# 03_Power.net
KiCad netlist of a schematic drawn in Altium Designer
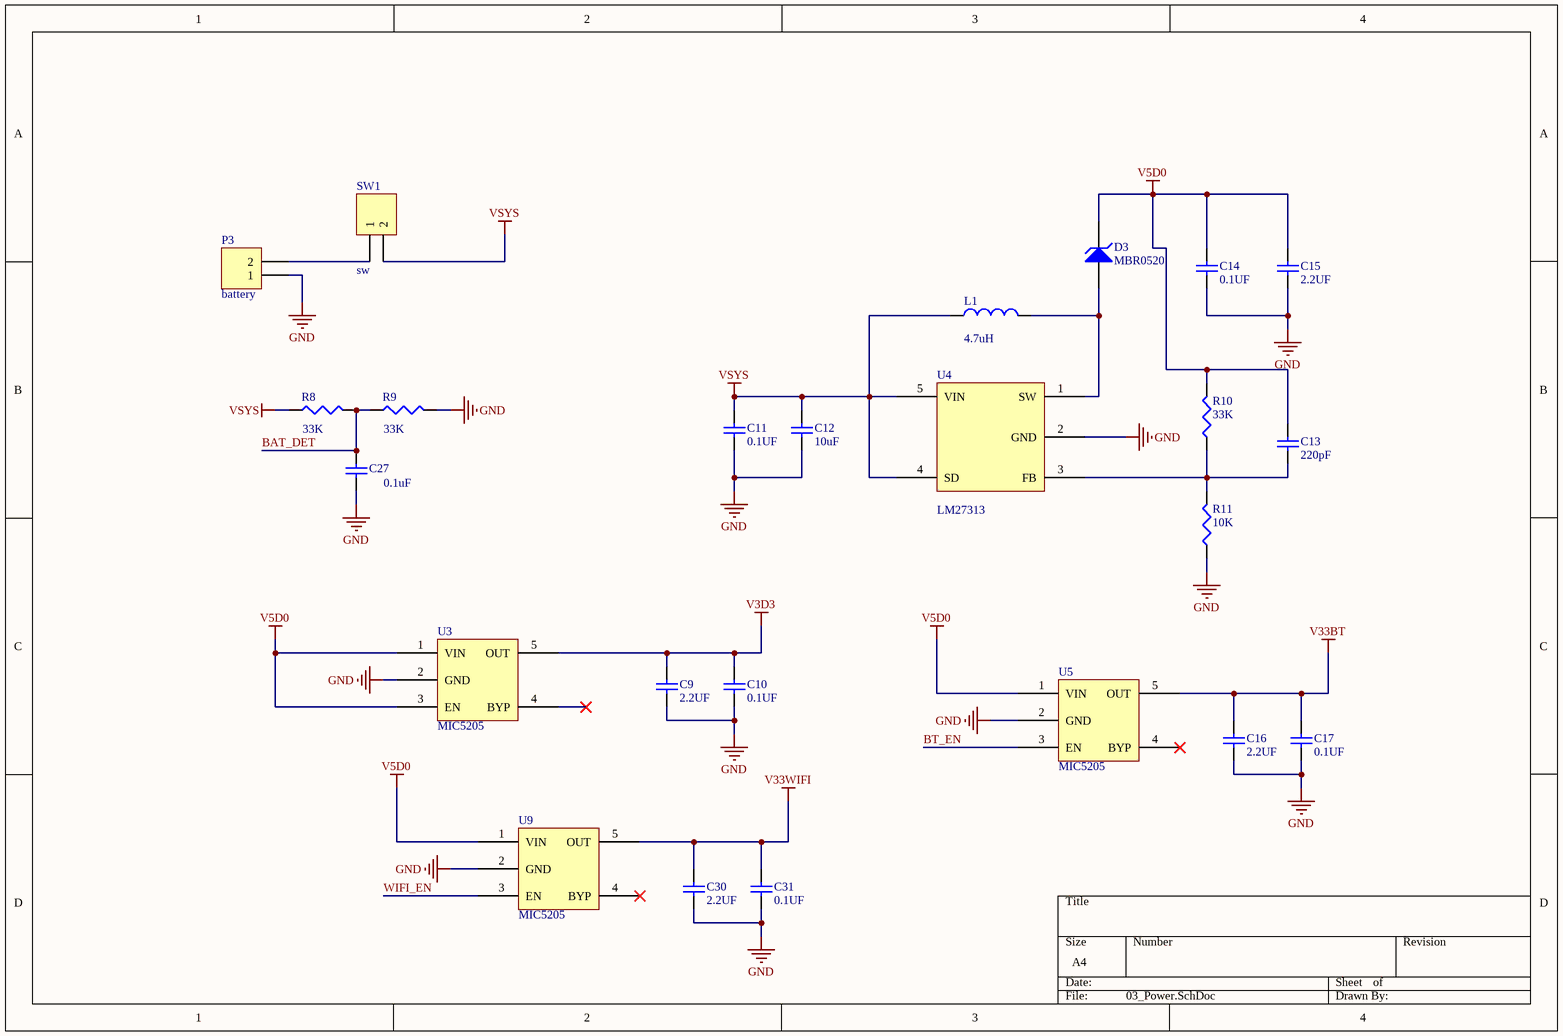
[diagram p0: 03_Power.SchDoc]

(export (version "E")
  (design (tool "Eeschema 10.0.6"))
  (components
    (comp (ref "C9")
      (value "2.2UF")
      (footprint "0402")
      (description "Capacitor")
      (fields (field (name "Comment") "Cap") (field (name "PUBLISHER") "Altium Limited"))
      (libsource (lib "Miscellaneous Devices") (part "Cap"))
    )
    (comp (ref "C10")
      (value "0.1UF")
      (footprint "0402")
      (description "Capacitor")
      (fields (field (name "Comment") "Cap") (field (name "PUBLISHER") "Altium Limited"))
      (libsource (lib "Miscellaneous Devices") (part "Cap"))
    )
    (comp (ref "C11")
      (value "0.1UF")
      (footprint "0402")
      (description "Capacitor")
      (fields (field (name "Comment") "Cap") (field (name "PUBLISHER") "Altium Limited"))
      (libsource (lib "Miscellaneous Devices") (part "Cap"))
    )
    (comp (ref "C12")
      (value "10uF")
      (footprint "0402")
      (description "Capacitor")
      (fields (field (name "Comment") "Cap") (field (name "PUBLISHER") "Altium Limited"))
      (libsource (lib "Miscellaneous Devices") (part "Cap"))
    )
    (comp (ref "C13")
      (value "220pF")
      (footprint "0402")
      (description "Capacitor")
      (fields (field (name "Comment") "Cap") (field (name "PUBLISHER") "Altium Limited"))
      (libsource (lib "Miscellaneous Devices") (part "Cap"))
    )
    (comp (ref "C14")
      (value "0.1UF")
      (footprint "0402")
      (description "Capacitor")
      (fields (field (name "Comment") "Cap") (field (name "PUBLISHER") "Altium Limited"))
      (libsource (lib "Miscellaneous Devices") (part "Cap"))
    )
    (comp (ref "C15")
      (value "2.2UF")
      (footprint "0402")
      (description "Capacitor")
      (fields (field (name "Comment") "Cap") (field (name "PUBLISHER") "Altium Limited"))
      (libsource (lib "Miscellaneous Devices") (part "Cap"))
    )
    (comp (ref "C16")
      (value "2.2UF")
      (footprint "0402")
      (description "Capacitor")
      (fields (field (name "Comment") "Cap") (field (name "PUBLISHER") "Altium Limited"))
      (libsource (lib "Miscellaneous Devices") (part "Cap"))
    )
    (comp (ref "C17")
      (value "0.1UF")
      (footprint "0402")
      (description "Capacitor")
      (fields (field (name "Comment") "Cap") (field (name "PUBLISHER") "Altium Limited"))
      (libsource (lib "Miscellaneous Devices") (part "Cap"))
    )
    (comp (ref "C27")
      (value "0.1uF")
      (footprint "0402")
      (description "Capacitor")
      (fields (field (name "Comment") "Cap") (field (name "PUBLISHER") "Altium Limited"))
      (libsource (lib "Miscellaneous Devices") (part "Cap"))
    )
    (comp (ref "C30")
      (value "2.2UF")
      (footprint "0402")
      (description "Capacitor")
      (fields (field (name "Comment") "Cap") (field (name "PUBLISHER") "Altium Limited"))
      (libsource (lib "Miscellaneous Devices") (part "Cap"))
    )
    (comp (ref "C31")
      (value "0.1UF")
      (footprint "0402")
      (description "Capacitor")
      (fields (field (name "Comment") "Cap") (field (name "PUBLISHER") "Altium Limited"))
      (libsource (lib "Miscellaneous Devices") (part "Cap"))
    )
    (comp (ref "D3")
      (value "MBR0520")
      (footprint "6-0805_N")
      (description "Zener Diode")
      (fields (field (name "PUBLISHER") "Altium Limited"))
      (libsource (lib "Miscellaneous Devices") (part "D Zener"))
    )
    (comp (ref "L1")
      (value "4.7uH")
      (footprint "0402-A")
      (description "Inductor")
      (fields (field (name "PUBLISHER") "Altium Limited"))
      (libsource (lib "Miscellaneous Devices") (part "Inductor"))
    )
    (comp (ref "P3")
      (value "battery")
      (footprint "HDR1X2")
      (description "Header, 2-Pin")
      (fields (field (name "PUBLISHER") "Altium Limited"))
      (libsource (lib "") (part "Header 2_1"))
    )
    (comp (ref "R8")
      (value "33K")
      (footprint "0402")
      (description "Resistor")
      (fields (field (name "Comment") "Res3") (field (name "PUBLISHER") "Altium Limited"))
      (libsource (lib "Miscellaneous Devices") (part "Res3"))
    )
    (comp (ref "R9")
      (value "33K")
      (footprint "0402")
      (description "Resistor")
      (fields (field (name "Comment") "Res3") (field (name "PUBLISHER") "Altium Limited"))
      (libsource (lib "Miscellaneous Devices") (part "Res3"))
    )
    (comp (ref "R10")
      (value "33K")
      (footprint "0402")
      (description "Resistor")
      (fields (field (name "Comment") "Res3") (field (name "PUBLISHER") "Altium Limited"))
      (libsource (lib "Miscellaneous Devices") (part "Res3"))
    )
    (comp (ref "R11")
      (value "10K")
      (footprint "0402")
      (description "Resistor")
      (fields (field (name "Comment") "Res3") (field (name "PUBLISHER") "Altium Limited"))
      (libsource (lib "Miscellaneous Devices") (part "Res3"))
    )
    (comp (ref "SW1")
      (value "sw")
      (footprint "HDR1X2")
      (description "Header, 2-Pin")
      (fields (field (name "PUBLISHER") "Altium Limited"))
      (libsource (lib "Miscellaneous Connectors") (part "Header 2"))
    )
    (comp (ref "U3")
      (value "MIC5205")
      (footprint "SOT25-5")
      (libsource (lib "aircraftschlib") (part "MIC5205"))
    )
    (comp (ref "U4")
      (value "LM27313")
      (footprint "SOT25-5")
      (libsource (lib "aircraftschlib") (part "LM27313"))
    )
    (comp (ref "U5")
      (value "MIC5205")
      (footprint "SOT25-5")
      (libsource (lib "aircraftschlib") (part "MIC5205"))
    )
    (comp (ref "U9")
      (value "MIC5205")
      (footprint "SOT25-5")
      (libsource (lib "aircraftschlib") (part "MIC5205"))
    )
  )
  (nets
    (net (code "1") (name "/BAT_DET") (class "Default")
      (node (ref "C27") (pin "2") (pinfunction "2_2") (pintype "passive"))
      (node (ref "R8") (pin "2") (pinfunction "2_2") (pintype "passive"))
      (node (ref "R9") (pin "1") (pinfunction "1_1") (pintype "passive"))
    )
    (net (code "2") (name "/BT_EN") (class "Default")
      (node (ref "U5") (pin "3") (pinfunction "EN_3") (pintype "passive"))
    )
    (net (code "3") (name "/WIFI_EN") (class "Default")
      (node (ref "U9") (pin "3") (pinfunction "EN_3") (pintype "passive"))
    )
    (net (code "4") (name "GND") (class "Default")
      (node (ref "C10") (pin "2") (pinfunction "2_2") (pintype "passive"))
      (node (ref "C11") (pin "2") (pinfunction "2_2") (pintype "passive"))
      (node (ref "C12") (pin "2") (pinfunction "2_2") (pintype "passive"))
      (node (ref "C14") (pin "2") (pinfunction "2_2") (pintype "passive"))
      (node (ref "C15") (pin "2") (pinfunction "2_2") (pintype "passive"))
      (node (ref "C16") (pin "2") (pinfunction "2_2") (pintype "passive"))
      (node (ref "C17") (pin "2") (pinfunction "2_2") (pintype "passive"))
      (node (ref "C27") (pin "1") (pinfunction "1_1") (pintype "passive"))
      (node (ref "C30") (pin "2") (pinfunction "2_2") (pintype "passive"))
      (node (ref "C31") (pin "2") (pinfunction "2_2") (pintype "passive"))
      (node (ref "C9") (pin "2") (pinfunction "2_2") (pintype "passive"))
      (node (ref "P3") (pin "1") (pinfunction "1_1") (pintype "passive"))
      (node (ref "R11") (pin "1") (pinfunction "1_1") (pintype "passive"))
      (node (ref "R9") (pin "2") (pinfunction "2_2") (pintype "passive"))
      (node (ref "U3") (pin "2") (pinfunction "GND_2") (pintype "passive"))
      (node (ref "U4") (pin "2") (pinfunction "GND_2") (pintype "passive"))
      (node (ref "U5") (pin "2") (pinfunction "GND_2") (pintype "passive"))
      (node (ref "U9") (pin "2") (pinfunction "GND_2") (pintype "passive"))
    )
    (net (code "5") (name "Net-(D3-A)") (class "Default")
      (node (ref "D3") (pin "1") (pinfunction "A_1") (pintype "passive"))
      (node (ref "L1") (pin "2") (pinfunction "2_2") (pintype "passive"))
      (node (ref "U4") (pin "1") (pinfunction "SW_1") (pintype "passive"))
    )
    (net (code "6") (name "Net-(P3-Pad2)") (class "Default")
      (node (ref "P3") (pin "2") (pinfunction "2_2") (pintype "passive"))
      (node (ref "SW1") (pin "1") (pinfunction "1_1") (pintype "passive"))
    )
    (net (code "7") (name "Net-(U4-FB)") (class "Default")
      (node (ref "C13") (pin "2") (pinfunction "2_2") (pintype "passive"))
      (node (ref "R10") (pin "1") (pinfunction "1_1") (pintype "passive"))
      (node (ref "R11") (pin "2") (pinfunction "2_2") (pintype "passive"))
      (node (ref "U4") (pin "3") (pinfunction "FB_3") (pintype "passive"))
    )
    (net (code "8") (name "V3D3") (class "Default")
      (node (ref "C10") (pin "1") (pinfunction "1_1") (pintype "passive"))
      (node (ref "C9") (pin "1") (pinfunction "1_1") (pintype "passive"))
      (node (ref "U3") (pin "5") (pinfunction "OUT_5") (pintype "passive"))
    )
    (net (code "9") (name "V5D0") (class "Default")
      (node (ref "C13") (pin "1") (pinfunction "1_1") (pintype "passive"))
      (node (ref "C14") (pin "1") (pinfunction "1_1") (pintype "passive"))
      (node (ref "C15") (pin "1") (pinfunction "1_1") (pintype "passive"))
      (node (ref "D3") (pin "2") (pinfunction "K_2") (pintype "passive"))
      (node (ref "R10") (pin "2") (pinfunction "2_2") (pintype "passive"))
      (node (ref "U3") (pin "1") (pinfunction "VIN_1") (pintype "passive"))
      (node (ref "U3") (pin "3") (pinfunction "EN_3") (pintype "passive"))
      (node (ref "U5") (pin "1") (pinfunction "VIN_1") (pintype "passive"))
      (node (ref "U9") (pin "1") (pinfunction "VIN_1") (pintype "passive"))
    )
    (net (code "10") (name "V33BT") (class "Default")
      (node (ref "C16") (pin "1") (pinfunction "1_1") (pintype "passive"))
      (node (ref "C17") (pin "1") (pinfunction "1_1") (pintype "passive"))
      (node (ref "U5") (pin "5") (pinfunction "OUT_5") (pintype "passive"))
    )
    (net (code "11") (name "V33WIFI") (class "Default")
      (node (ref "C30") (pin "1") (pinfunction "1_1") (pintype "passive"))
      (node (ref "C31") (pin "1") (pinfunction "1_1") (pintype "passive"))
      (node (ref "U9") (pin "5") (pinfunction "OUT_5") (pintype "passive"))
    )
    (net (code "12") (name "VSYS") (class "Default")
      (node (ref "C11") (pin "1") (pinfunction "1_1") (pintype "passive"))
      (node (ref "C12") (pin "1") (pinfunction "1_1") (pintype "passive"))
      (node (ref "L1") (pin "1") (pinfunction "1_1") (pintype "passive"))
      (node (ref "R8") (pin "1") (pinfunction "1_1") (pintype "passive"))
      (node (ref "SW1") (pin "2") (pinfunction "2_2") (pintype "passive"))
      (node (ref "U4") (pin "4") (pinfunction "SD_4") (pintype "passive"))
      (node (ref "U4") (pin "5") (pinfunction "VIN_5") (pintype "passive"))
    )
    (net (code "13") (name "unconnected-(U3-BYP-Pad4)") (class "Default")
      (node (ref "U3") (pin "4") (pinfunction "BYP_4") (pintype "passive+no_connect"))
    )
    (net (code "14") (name "unconnected-(U5-BYP-Pad4)") (class "Default")
      (node (ref "U5") (pin "4") (pinfunction "BYP_4") (pintype "passive+no_connect"))
    )
    (net (code "15") (name "unconnected-(U9-BYP-Pad4)") (class "Default")
      (node (ref "U9") (pin "4") (pinfunction "BYP_4") (pintype "passive+no_connect"))
    )
  )
)
